# Environment-TinyPICO-Mini-Enclosure-V9.net
KiCad netlist of a schematic drawn in EAGLE
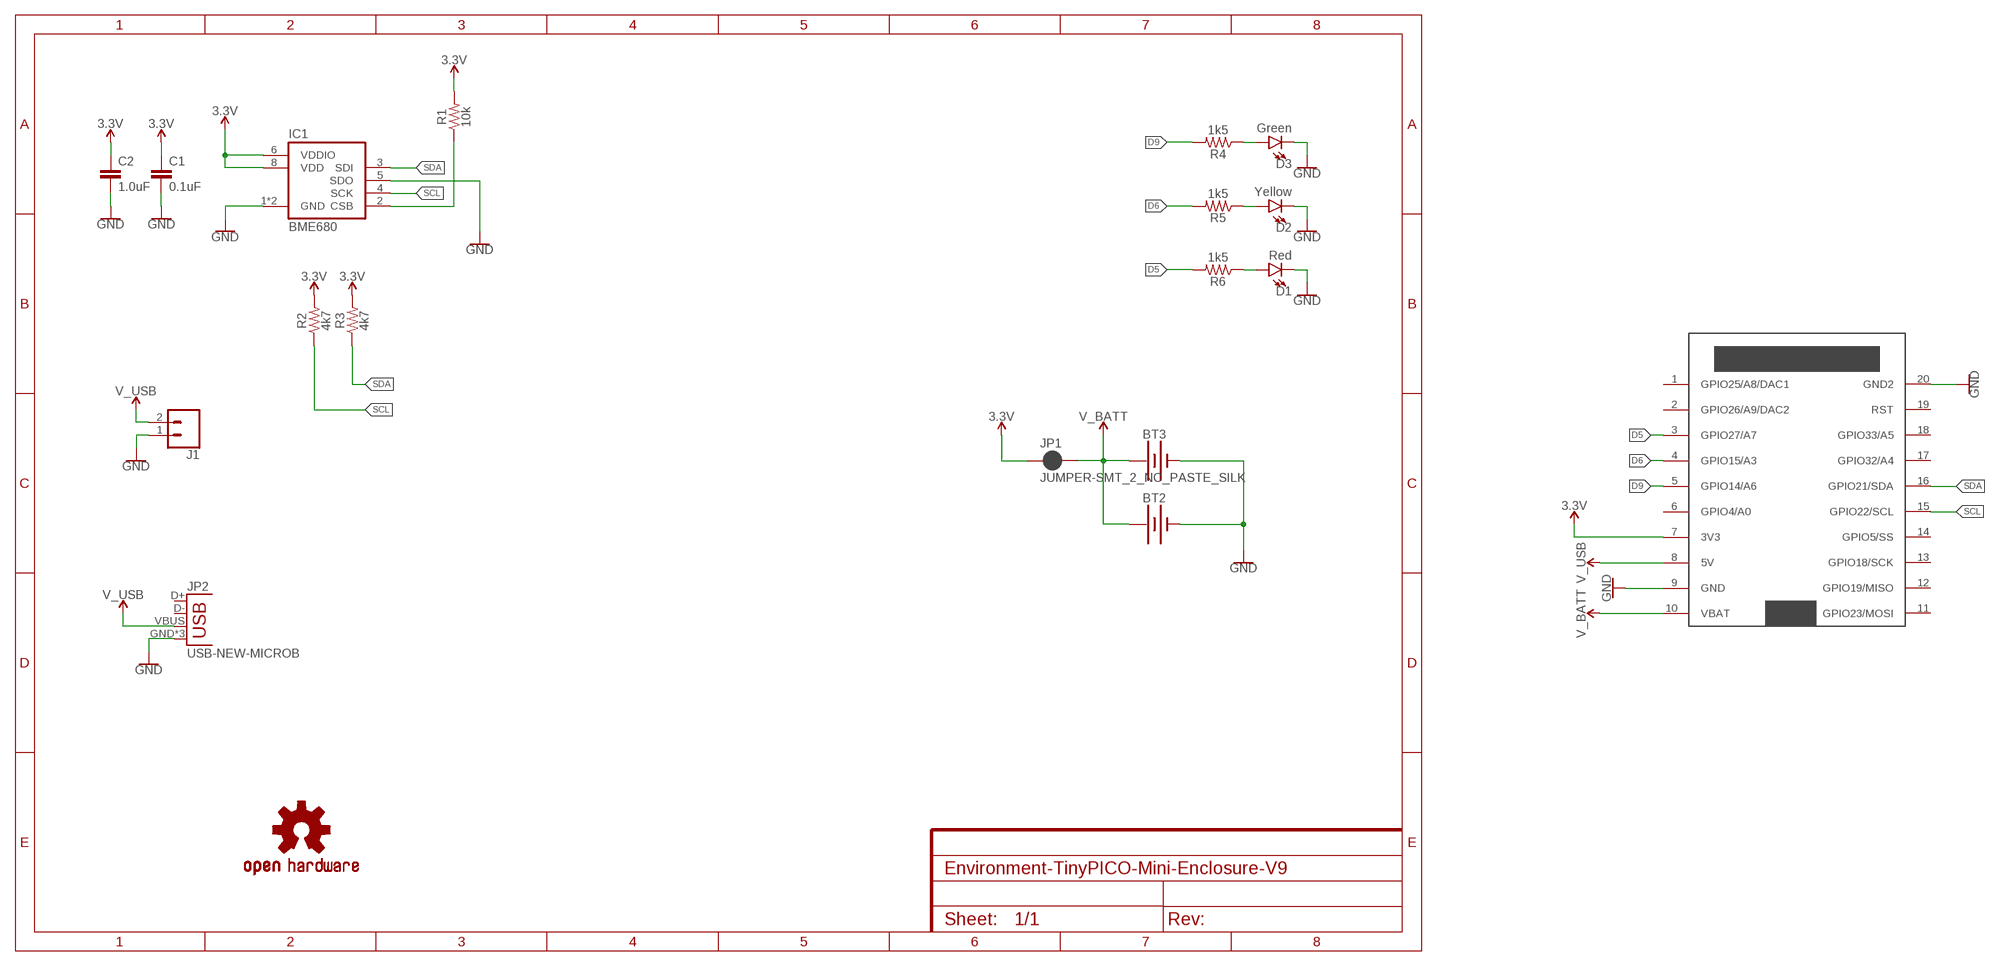
[diagram p0: schematic, sheet 1]

(export (version "E")
  (design (tool "Eeschema 10.0.6"))
  (components
    (comp (ref "BT2")
      (value "BATTERY-12MM_PTH")
      (footprint "eagle-import:BATTCON_12MM_PTH")
      (libsource (lib "eagle-import") (part "BATTERY-12MM_PTH"))
    )
    (comp (ref "BT3")
      (value "BATTERY-12MM_PTH")
      (footprint "eagle-import:BATTCON_12MM_PTH")
      (libsource (lib "eagle-import") (part "BATTERY-12MM_PTH"))
    )
    (comp (ref "C1")
      (value "0.1uF")
      (footprint "eagle-import:0805")
      (libsource (lib "eagle-import") (part "0.1UF-0805-25V"))
    )
    (comp (ref "C2")
      (value "1.0uF")
      (footprint "eagle-import:0805")
      (libsource (lib "eagle-import") (part "1.0UF-0805-25V-10%"))
    )
    (comp (ref "D1")
      (value "Red")
      (footprint "eagle-import:LED-1206")
      (libsource (lib "eagle-import") (part "LED1206"))
    )
    (comp (ref "D2")
      (value "Yellow")
      (footprint "eagle-import:LED-1206")
      (libsource (lib "eagle-import") (part "LED1206"))
    )
    (comp (ref "D3")
      (value "Green")
      (footprint "eagle-import:LED-1206")
      (libsource (lib "eagle-import") (part "LED1206"))
    )
    (comp (ref "IC1")
      (value "BME680")
      (footprint "eagle-import:BME680")
      (libsource (lib "eagle-import") (part "BME680"))
    )
    (comp (ref "J1")
      (value "CONN_02JST-2-PH-SIDE")
      (footprint "eagle-import:JST-2-SMD")
      (libsource (lib "eagle-import") (part "CONN_02JST-2-PH-SIDE"))
    )
    (comp (ref "JP1")
      (value "JUMPER-SMT_2_NC_PASTE_SILK")
      (footprint "eagle-import:SMT-JUMPER_2_NC_PASTE_SILK")
      (libsource (lib "eagle-import") (part "JUMPER-SMT_2_NC_PASTE_SILK"))
    )
    (comp (ref "JP2")
      (value "USB-NEW-MICROB")
      (footprint "eagle-import:USB-MICROB")
      (libsource (lib "eagle-import") (part "USB-NEW-MICROB"))
    )
    (comp (ref "LOGO1")
      (value "OSHW-LOGOM")
      (footprint "eagle-import:OSHW-LOGO-M")
      (libsource (lib "eagle-import") (part "OSHW-LOGOM"))
    )
    (comp (ref "R1")
      (value "10k")
      (footprint "eagle-import:0805")
      (libsource (lib "eagle-import") (part "RESISTOR0805"))
    )
    (comp (ref "R2")
      (value "4k7")
      (footprint "eagle-import:0805")
      (libsource (lib "eagle-import") (part "RESISTOR0805"))
    )
    (comp (ref "R3")
      (value "4k7")
      (footprint "eagle-import:0805")
      (libsource (lib "eagle-import") (part "RESISTOR0805"))
    )
    (comp (ref "R4")
      (value "1k5")
      (footprint "eagle-import:0805")
      (libsource (lib "eagle-import") (part "RESISTOR0805"))
    )
    (comp (ref "R5")
      (value "1k5")
      (footprint "eagle-import:0805")
      (libsource (lib "eagle-import") (part "RESISTOR0805"))
    )
    (comp (ref "R6")
      (value "1k5")
      (footprint "eagle-import:0805")
      (libsource (lib "eagle-import") (part "RESISTOR0805"))
    )
    (comp (ref "U$2")
      (value "TINY_PICO")
      (footprint "eagle-import:TINY_PICO")
      (libsource (lib "eagle-import") (part "TINY_PICO"))
    )
  )
  (nets
    (net (code "1") (name "3.3V") (class "Default")
      (node (ref "C1") (pin "1") (pinfunction "1_1") (pintype "passive"))
      (node (ref "C2") (pin "1") (pinfunction "1_1") (pintype "passive"))
      (node (ref "IC1") (pin "6") (pinfunction "VDDIO_6") (pintype "power_in"))
      (node (ref "IC1") (pin "8") (pinfunction "VDD_8") (pintype "power_in"))
      (node (ref "JP1") (pin "1") (pinfunction "1_1") (pintype "passive"))
      (node (ref "R1") (pin "2") (pinfunction "2_2") (pintype "passive"))
      (node (ref "R2") (pin "2") (pinfunction "2_2") (pintype "passive"))
      (node (ref "R3") (pin "2") (pinfunction "2_2") (pintype "passive"))
      (node (ref "U$2") (pin "7") (pinfunction "3V3_7") (pintype "power_in"))
    )
    (net (code "2") (name "D5") (class "Default")
      (node (ref "R6") (pin "2") (pinfunction "2_2") (pintype "passive"))
      (node (ref "U$2") (pin "3") (pinfunction "GPIO27/A7_3") (pintype "bidirectional"))
    )
    (net (code "3") (name "D6") (class "Default")
      (node (ref "R5") (pin "2") (pinfunction "2_2") (pintype "passive"))
      (node (ref "U$2") (pin "4") (pinfunction "GPIO15/A3_4") (pintype "bidirectional"))
    )
    (net (code "4") (name "D9") (class "Default")
      (node (ref "R4") (pin "2") (pinfunction "2_2") (pintype "passive"))
      (node (ref "U$2") (pin "5") (pinfunction "GPIO14/A6_5") (pintype "bidirectional"))
    )
    (net (code "5") (name "GND") (class "Default")
      (node (ref "BT2") (pin "GND") (pinfunction "-_GND") (pintype "power_in"))
      (node (ref "BT3") (pin "GND") (pinfunction "-_GND") (pintype "power_in"))
      (node (ref "C1") (pin "2") (pinfunction "2_2") (pintype "passive"))
      (node (ref "C2") (pin "2") (pinfunction "2_2") (pintype "passive"))
      (node (ref "D1") (pin "C") (pinfunction "C_C") (pintype "passive"))
      (node (ref "D2") (pin "C") (pinfunction "C_C") (pintype "passive"))
      (node (ref "D3") (pin "C") (pinfunction "C_C") (pintype "passive"))
      (node (ref "IC1") (pin "1") (pinfunction "GND_1") (pintype "power_in"))
      (node (ref "IC1") (pin "5") (pinfunction "SDO_5") (pintype "output"))
      (node (ref "IC1") (pin "7") (pinfunction "GND_7") (pintype "power_in"))
      (node (ref "J1") (pin "1") (pinfunction "2_1") (pintype "passive"))
      (node (ref "JP2") (pin "GND") (pinfunction "GND_GND") (pintype "bidirectional"))
      (node (ref "JP2") (pin "MT1") (pinfunction "GND_MT1") (pintype "bidirectional"))
      (node (ref "JP2") (pin "MT2") (pinfunction "GND_MT2") (pintype "bidirectional"))
      (node (ref "U$2") (pin "20") (pinfunction "GND2_20") (pintype "bidirectional"))
      (node (ref "U$2") (pin "9") (pinfunction "GND_9") (pintype "power_in"))
    )
    (net (code "6") (name "Net-(D1-PadA)") (class "Default")
      (node (ref "D1") (pin "A") (pinfunction "A_A") (pintype "passive"))
      (node (ref "R6") (pin "1") (pinfunction "1_1") (pintype "passive"))
    )
    (net (code "7") (name "Net-(D2-PadA)") (class "Default")
      (node (ref "D2") (pin "A") (pinfunction "A_A") (pintype "passive"))
      (node (ref "R5") (pin "1") (pinfunction "1_1") (pintype "passive"))
    )
    (net (code "8") (name "Net-(D3-PadA)") (class "Default")
      (node (ref "D3") (pin "A") (pinfunction "A_A") (pintype "passive"))
      (node (ref "R4") (pin "1") (pinfunction "1_1") (pintype "passive"))
    )
    (net (code "9") (name "Net-(IC1-CSB)") (class "Default")
      (node (ref "IC1") (pin "2") (pinfunction "CSB_2") (pintype "input"))
      (node (ref "R1") (pin "1") (pinfunction "1_1") (pintype "passive"))
    )
    (net (code "10") (name "SCL") (class "Default")
      (node (ref "IC1") (pin "4") (pinfunction "SCK_4") (pintype "input"))
      (node (ref "R2") (pin "1") (pinfunction "1_1") (pintype "passive"))
      (node (ref "U$2") (pin "15") (pinfunction "GPIO22/SCL_15") (pintype "bidirectional"))
    )
    (net (code "11") (name "SDA") (class "Default")
      (node (ref "IC1") (pin "3") (pinfunction "SDI_3") (pintype "input"))
      (node (ref "R3") (pin "1") (pinfunction "1_1") (pintype "passive"))
      (node (ref "U$2") (pin "16") (pinfunction "GPIO21/SDA_16") (pintype "bidirectional"))
    )
    (net (code "12") (name "V_BATT") (class "Default")
      (node (ref "BT2") (pin "VCC@1") (pinfunction "+_VCC@1") (pintype "power_in"))
      (node (ref "BT3") (pin "VCC@1") (pinfunction "+_VCC@1") (pintype "power_in"))
      (node (ref "JP1") (pin "2") (pinfunction "2_2") (pintype "passive"))
      (node (ref "U$2") (pin "10") (pinfunction "VBAT_10") (pintype "power_in"))
    )
    (net (code "13") (name "V_USB") (class "Default")
      (node (ref "J1") (pin "2") (pinfunction "1_2") (pintype "passive"))
      (node (ref "JP2") (pin "VBUS") (pinfunction "VBUS_VBUS") (pintype "bidirectional"))
      (node (ref "U$2") (pin "8") (pinfunction "5V_8") (pintype "power_in"))
    )
    (net (code "14") (name "unconnected-(JP2-PadD+)") (class "Default")
      (node (ref "JP2") (pin "D+") (pinfunction "D+_D+") (pintype "bidirectional"))
    )
    (net (code "15") (name "unconnected-(JP2-PadD-)") (class "Default")
      (node (ref "JP2") (pin "D-") (pinfunction "D-_D-") (pintype "bidirectional"))
    )
    (net (code "16") (name "unconnected-(U$2-GPIO4{slash}A0-Pad6)") (class "Default")
      (node (ref "U$2") (pin "6") (pinfunction "GPIO4/A0_6") (pintype "bidirectional"))
    )
    (net (code "17") (name "unconnected-(U$2-GPIO5{slash}SS-Pad14)") (class "Default")
      (node (ref "U$2") (pin "14") (pinfunction "GPIO5/SS_14") (pintype "bidirectional"))
    )
    (net (code "18") (name "unconnected-(U$2-GPIO18{slash}SCK-Pad13)") (class "Default")
      (node (ref "U$2") (pin "13") (pinfunction "GPIO18/SCK_13") (pintype "bidirectional"))
    )
    (net (code "19") (name "unconnected-(U$2-GPIO19{slash}MISO-Pad12)") (class "Default")
      (node (ref "U$2") (pin "12") (pinfunction "GPIO19/MISO_12") (pintype "bidirectional"))
    )
    (net (code "20") (name "unconnected-(U$2-GPIO23{slash}MOSI-Pad11)") (class "Default")
      (node (ref "U$2") (pin "11") (pinfunction "GPIO23/MOSI_11") (pintype "bidirectional"))
    )
    (net (code "21") (name "unconnected-(U$2-GPIO25{slash}A8{slash}DAC1-Pad1)") (class "Default")
      (node (ref "U$2") (pin "1") (pinfunction "GPIO25/A8/DAC1_1") (pintype "bidirectional"))
    )
    (net (code "22") (name "unconnected-(U$2-GPIO26{slash}A9{slash}DAC2-Pad2)") (class "Default")
      (node (ref "U$2") (pin "2") (pinfunction "GPIO26/A9/DAC2_2") (pintype "bidirectional"))
    )
    (net (code "23") (name "unconnected-(U$2-GPIO32{slash}A4-Pad17)") (class "Default")
      (node (ref "U$2") (pin "17") (pinfunction "GPIO32/A4_17") (pintype "bidirectional"))
    )
    (net (code "24") (name "unconnected-(U$2-GPIO33{slash}A5-Pad18)") (class "Default")
      (node (ref "U$2") (pin "18") (pinfunction "GPIO33/A5_18") (pintype "bidirectional"))
    )
    (net (code "25") (name "unconnected-(U$2-RST-Pad19)") (class "Default")
      (node (ref "U$2") (pin "19") (pinfunction "RST_19") (pintype "input"))
    )
  )
)
